# ALAYOUT.net
KiCad netlist of a schematic drawn in EAGLE
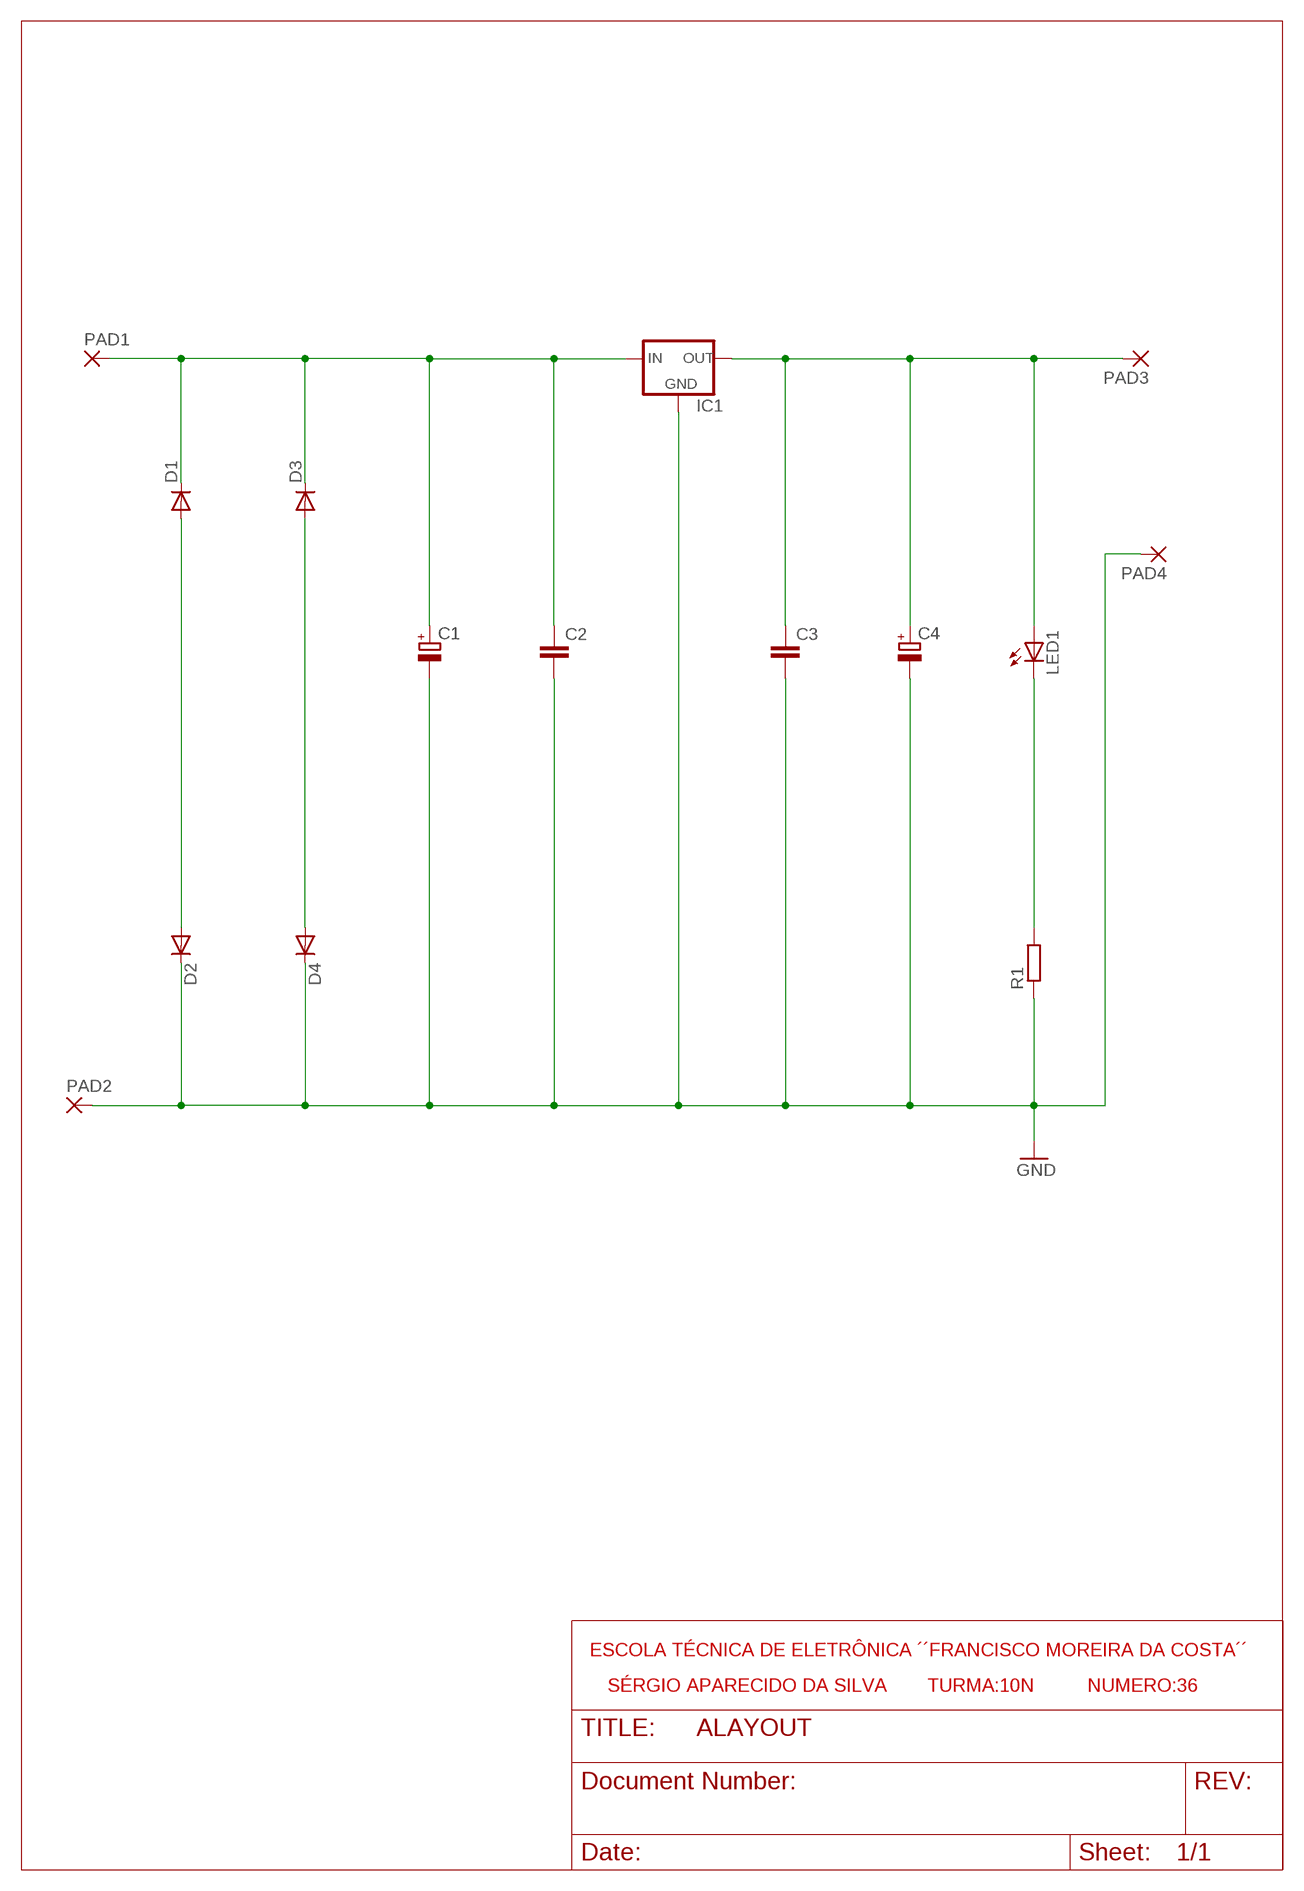
[diagram p0: schematic, sheet 1]

(export (version "E")
  (design (tool "Eeschema 10.0.6"))
  (components
    (comp (ref "C1")
      (value "CPOL-EUE7.5-16")
      (footprint "eagle-import:E7,5-16")
      (libsource (lib "eagle-import") (part "CPOL-EUE7.5-16"))
    )
    (comp (ref "C2")
      (value "C-EU050-030X075")
      (footprint "eagle-import:C050-030X075")
      (libsource (lib "eagle-import") (part "C-EU050-030X075"))
    )
    (comp (ref "C3")
      (value "C-EU050-030X075")
      (footprint "eagle-import:C050-030X075")
      (libsource (lib "eagle-import") (part "C-EU050-030X075"))
    )
    (comp (ref "C4")
      (value "CPOL-EUE5-8.5")
      (footprint "eagle-import:E5-8,5")
      (libsource (lib "eagle-import") (part "CPOL-EUE5-8.5"))
    )
    (comp (ref "D1")
      (value "DIODE-DO35-10")
      (footprint "eagle-import:DO35-10")
      (libsource (lib "eagle-import") (part "DIODE-DO35-10"))
    )
    (comp (ref "D2")
      (value "DIODE-DO35-10")
      (footprint "eagle-import:DO35-10")
      (libsource (lib "eagle-import") (part "DIODE-DO35-10"))
    )
    (comp (ref "D3")
      (value "DIODE-DO35-10")
      (footprint "eagle-import:DO35-10")
      (libsource (lib "eagle-import") (part "DIODE-DO35-10"))
    )
    (comp (ref "D4")
      (value "DIODE-DO35-10")
      (footprint "eagle-import:DO35-10")
      (libsource (lib "eagle-import") (part "DIODE-DO35-10"))
    )
    (comp (ref "IC1")
      (value "78XXS")
      (footprint "eagle-import:78XXS")
      (libsource (lib "eagle-import") (part "78XXS"))
    )
    (comp (ref "LED1")
      (value "LED3MM")
      (footprint "eagle-import:LED3MM")
      (libsource (lib "eagle-import") (part "LED3MM"))
    )
    (comp (ref "PAD1")
      (value "3,17/1,1")
      (footprint "eagle-import:3,17_1,1")
      (libsource (lib "eagle-import") (part "3,17/1,1"))
    )
    (comp (ref "PAD2")
      (value "3,17/1,1")
      (footprint "eagle-import:3,17_1,1")
      (libsource (lib "eagle-import") (part "3,17/1,1"))
    )
    (comp (ref "PAD3")
      (value "3,17/1,1")
      (footprint "eagle-import:3,17_1,1")
      (libsource (lib "eagle-import") (part "3,17/1,1"))
    )
    (comp (ref "PAD4")
      (value "3,17/1,1")
      (footprint "eagle-import:3,17_1,1")
      (libsource (lib "eagle-import") (part "3,17/1,1"))
    )
    (comp (ref "R1")
      (value "R-EU_0207/10")
      (footprint "eagle-import:0207_10")
      (libsource (lib "eagle-import") (part "R-EU_0207/10"))
    )
  )
  (nets
    (net (code "1") (name "GND") (class "Default")
      (node (ref "C1") (pin "-") (pinfunction "-_-") (pintype "passive"))
      (node (ref "C2") (pin "2") (pinfunction "2_2") (pintype "passive"))
      (node (ref "C3") (pin "2") (pinfunction "2_2") (pintype "passive"))
      (node (ref "C4") (pin "-") (pinfunction "-_-") (pintype "passive"))
      (node (ref "D2") (pin "C") (pinfunction "C_C") (pintype "passive"))
      (node (ref "D4") (pin "C") (pinfunction "C_C") (pintype "passive"))
      (node (ref "IC1") (pin "GND") (pinfunction "GND_GND") (pintype "input"))
      (node (ref "PAD2") (pin "1") (pinfunction "P_1") (pintype "passive"))
      (node (ref "PAD4") (pin "1") (pinfunction "P_1") (pintype "passive"))
      (node (ref "R1") (pin "1") (pinfunction "1_1") (pintype "passive"))
    )
    (net (code "2") (name "Net-(D1-PadA)") (class "Default")
      (node (ref "D1") (pin "A") (pinfunction "A_A") (pintype "passive"))
      (node (ref "D2") (pin "A") (pinfunction "A_A") (pintype "passive"))
    )
    (net (code "3") (name "Net-(D3-PadA)") (class "Default")
      (node (ref "D3") (pin "A") (pinfunction "A_A") (pintype "passive"))
      (node (ref "D4") (pin "A") (pinfunction "A_A") (pintype "passive"))
    )
    (net (code "4") (name "Net-(LED1-C)") (class "Default")
      (node (ref "LED1") (pin "K") (pinfunction "C_K") (pintype "passive"))
      (node (ref "R1") (pin "2") (pinfunction "2_2") (pintype "passive"))
    )
    (net (code "5") (name "Net-(PAD1-P)") (class "Default")
      (node (ref "C1") (pin "+") (pinfunction "+_+") (pintype "passive"))
      (node (ref "C2") (pin "1") (pinfunction "1_1") (pintype "passive"))
      (node (ref "D1") (pin "C") (pinfunction "C_C") (pintype "passive"))
      (node (ref "D3") (pin "C") (pinfunction "C_C") (pintype "passive"))
      (node (ref "IC1") (pin "IN") (pinfunction "IN_IN") (pintype "input"))
      (node (ref "PAD1") (pin "1") (pinfunction "P_1") (pintype "passive"))
    )
    (net (code "6") (name "Net-(PAD3-P)") (class "Default")
      (node (ref "C3") (pin "1") (pinfunction "1_1") (pintype "passive"))
      (node (ref "C4") (pin "+") (pinfunction "+_+") (pintype "passive"))
      (node (ref "IC1") (pin "OUT") (pinfunction "OUT_OUT") (pintype "passive"))
      (node (ref "LED1") (pin "A") (pinfunction "A_A") (pintype "passive"))
      (node (ref "PAD3") (pin "1") (pinfunction "P_1") (pintype "passive"))
    )
  )
)
